# RFBoardLayoutGen0_v03_1routing.net
KiCad netlist of a schematic drawn in EAGLE
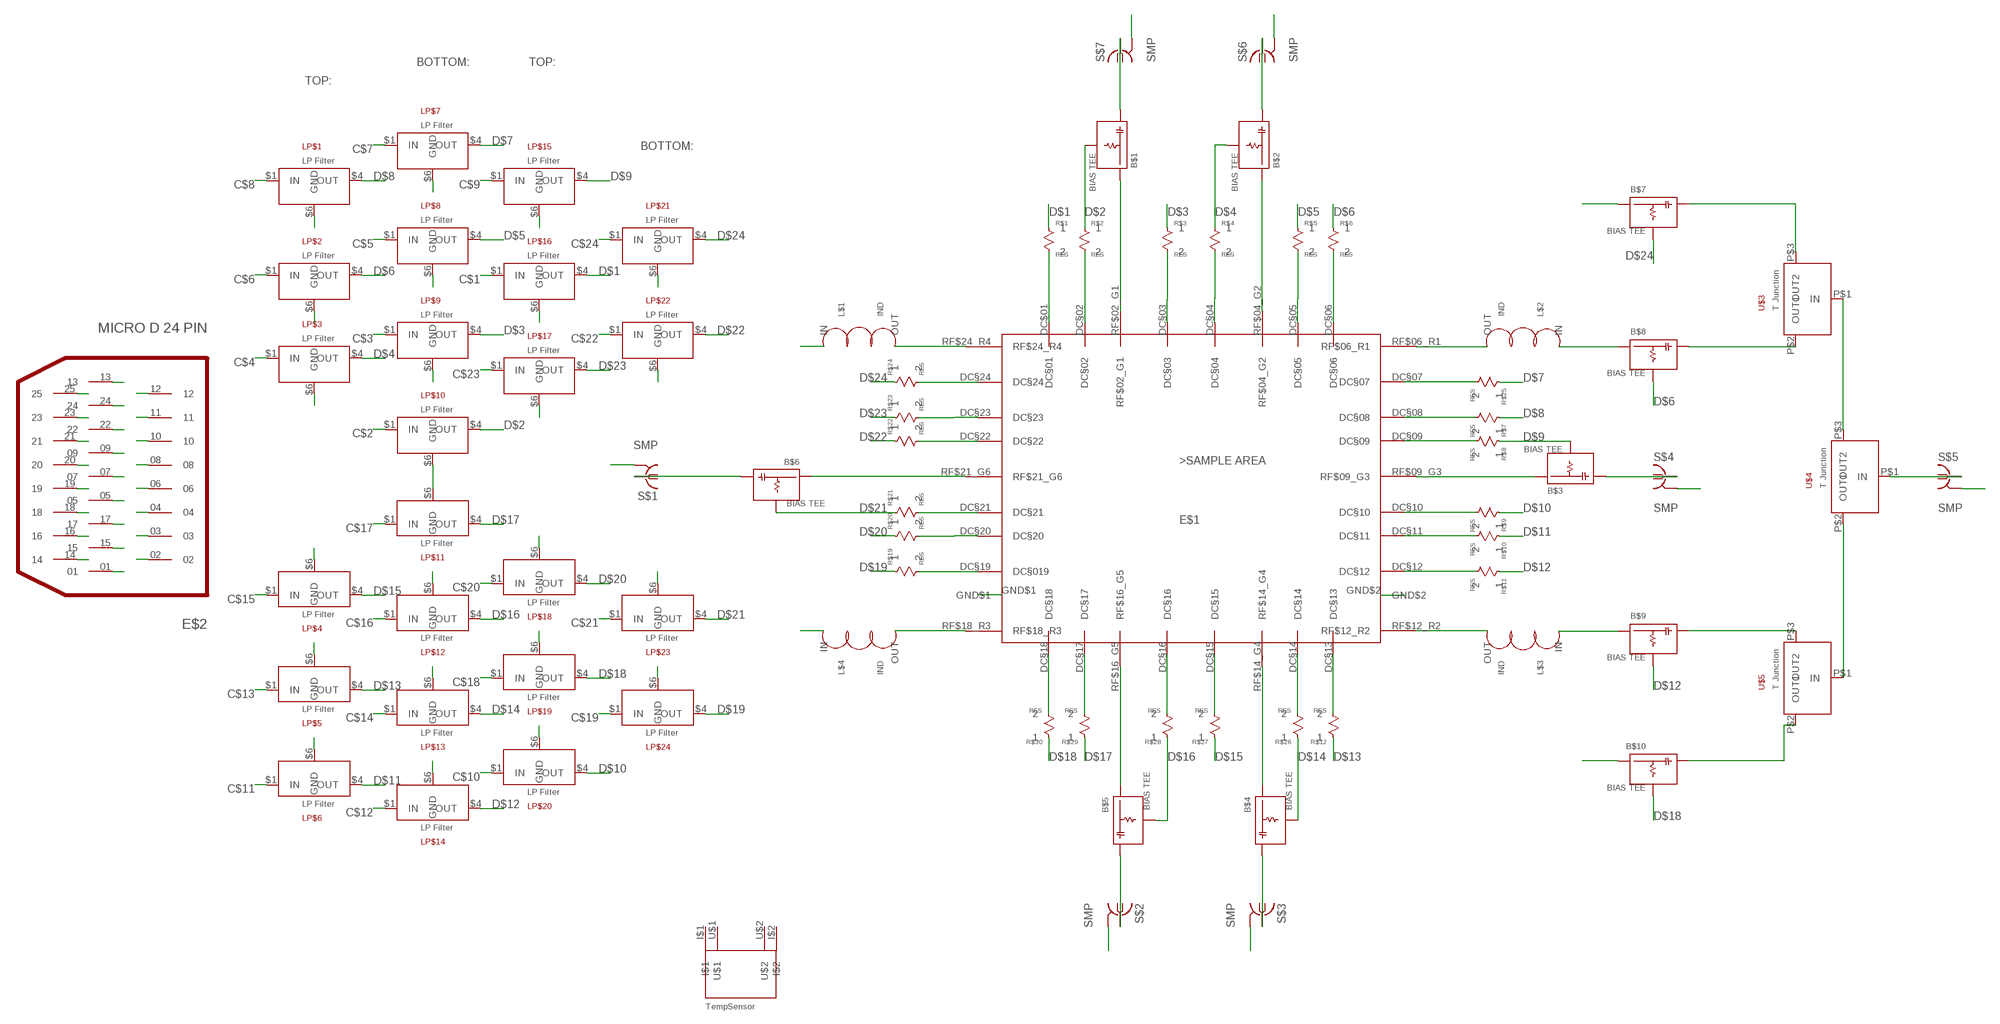
[diagram p0: schematic, sheet 1, part 1 of 2]
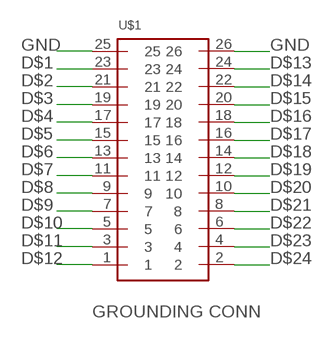
[diagram p1: schematic, sheet 1, part 2 of 2]

(export (version "E")
  (design (tool "Eeschema 10.0.6"))
  (components
    (comp (ref "B$1")
      (value "BIASTEEDOWN")
      (footprint "eagle-import:BIAS_TEE_DOWN_0603")
      (libsource (lib "eagle-import") (part "BIASTEEDOWN"))
    )
    (comp (ref "B$2")
      (value "BIASTEEUP")
      (footprint "eagle-import:BIAS_TEE_UP_0603")
      (libsource (lib "eagle-import") (part "BIASTEEUP"))
    )
    (comp (ref "B$3")
      (value "BIASTEEDOWN")
      (footprint "eagle-import:BIAS_TEE_DOWN_0603")
      (libsource (lib "eagle-import") (part "BIASTEEDOWN"))
    )
    (comp (ref "B$4")
      (value "BIASTEEDOWN")
      (footprint "eagle-import:BIAS_TEE_DOWN_0603")
      (libsource (lib "eagle-import") (part "BIASTEEDOWN"))
    )
    (comp (ref "B$5")
      (value "BIASTEEUP")
      (footprint "eagle-import:BIAS_TEE_UP_0603")
      (libsource (lib "eagle-import") (part "BIASTEEUP"))
    )
    (comp (ref "B$6")
      (value "BIASTEEDOWN")
      (footprint "eagle-import:BIAS_TEE_DOWN_0603")
      (libsource (lib "eagle-import") (part "BIASTEEDOWN"))
    )
    (comp (ref "B$7")
      (value "BIASTEEUP")
      (footprint "eagle-import:BIAS_TEE_UP_0603")
      (libsource (lib "eagle-import") (part "BIASTEEUP"))
    )
    (comp (ref "B$8")
      (value "BIASTEEDOWN")
      (footprint "eagle-import:BIAS_TEE_DOWN_0603")
      (libsource (lib "eagle-import") (part "BIASTEEDOWN"))
    )
    (comp (ref "B$9")
      (value "BIASTEEUP")
      (footprint "eagle-import:BIAS_TEE_UP_0603")
      (libsource (lib "eagle-import") (part "BIASTEEUP"))
    )
    (comp (ref "B$10")
      (value "BIASTEEDOWN")
      (footprint "eagle-import:BIAS_TEE_DOWN_0603")
      (libsource (lib "eagle-import") (part "BIASTEEDOWN"))
    )
    (comp (ref "E$1")
      (value "24DC+10RF")
      (footprint "eagle-import:24DC+10RF_400MU-PADS_0.7X0.7_V1.0")
      (libsource (lib "eagle-import") (part "24DC+10RF"))
    )
    (comp (ref "E$2")
      (value "25_SOCKET_M83513(13-DPINOUT2")
      (footprint "eagle-import:25_SOCKET_M83513_13-D_V2")
      (libsource (lib "eagle-import") (part "25_SOCKET_M83513(13-DPINOUT2"))
    )
    (comp (ref "L$1")
      (value "L_MATCH")
      (footprint "eagle-import:L_MATCH")
      (libsource (lib "eagle-import") (part "L_MATCH"))
    )
    (comp (ref "L$2")
      (value "L_MATCH")
      (footprint "eagle-import:L_MATCH")
      (libsource (lib "eagle-import") (part "L_MATCH"))
    )
    (comp (ref "L$3")
      (value "L_MATCH")
      (footprint "eagle-import:L_MATCH")
      (libsource (lib "eagle-import") (part "L_MATCH"))
    )
    (comp (ref "L$4")
      (value "L_MATCH")
      (footprint "eagle-import:L_MATCH")
      (libsource (lib "eagle-import") (part "L_MATCH"))
    )
    (comp (ref "LP$1")
      (value "LP-FILTER/1-STAGETOP")
      (footprint "eagle-import:LP-FILTER_1_STAGE_OS_0603_TOP")
      (libsource (lib "eagle-import") (part "LP-FILTER/1-STAGETOP"))
    )
    (comp (ref "LP$2")
      (value "LP-FILTER/1-STAGETOP")
      (footprint "eagle-import:LP-FILTER_1_STAGE_OS_0603_TOP")
      (libsource (lib "eagle-import") (part "LP-FILTER/1-STAGETOP"))
    )
    (comp (ref "LP$3")
      (value "LP-FILTER/1-STAGETOP")
      (footprint "eagle-import:LP-FILTER_1_STAGE_OS_0603_TOP")
      (libsource (lib "eagle-import") (part "LP-FILTER/1-STAGETOP"))
    )
    (comp (ref "LP$4")
      (value "LP-FILTER/1-STAGETOP")
      (footprint "eagle-import:LP-FILTER_1_STAGE_OS_0603_TOP")
      (libsource (lib "eagle-import") (part "LP-FILTER/1-STAGETOP"))
    )
    (comp (ref "LP$5")
      (value "LP-FILTER/1-STAGETOP")
      (footprint "eagle-import:LP-FILTER_1_STAGE_OS_0603_TOP")
      (libsource (lib "eagle-import") (part "LP-FILTER/1-STAGETOP"))
    )
    (comp (ref "LP$6")
      (value "LP-FILTER/1-STAGETOP")
      (footprint "eagle-import:LP-FILTER_1_STAGE_OS_0603_TOP")
      (libsource (lib "eagle-import") (part "LP-FILTER/1-STAGETOP"))
    )
    (comp (ref "LP$7")
      (value "LP-FILTER/1-STAGEBOT")
      (footprint "eagle-import:LP-FILTER_1_STAGE_OS_0603_BOTTOM")
      (libsource (lib "eagle-import") (part "LP-FILTER/1-STAGEBOT"))
    )
    (comp (ref "LP$8")
      (value "LP-FILTER/1-STAGEBOT")
      (footprint "eagle-import:LP-FILTER_1_STAGE_OS_0603_BOTTOM")
      (libsource (lib "eagle-import") (part "LP-FILTER/1-STAGEBOT"))
    )
    (comp (ref "LP$9")
      (value "LP-FILTER/1-STAGEBOT")
      (footprint "eagle-import:LP-FILTER_1_STAGE_OS_0603_BOTTOM")
      (libsource (lib "eagle-import") (part "LP-FILTER/1-STAGEBOT"))
    )
    (comp (ref "LP$10")
      (value "LP-FILTER/1-STAGEBOT")
      (footprint "eagle-import:LP-FILTER_1_STAGE_OS_0603_BOTTOM")
      (libsource (lib "eagle-import") (part "LP-FILTER/1-STAGEBOT"))
    )
    (comp (ref "LP$11")
      (value "LP-FILTER/1-STAGEBOT")
      (footprint "eagle-import:LP-FILTER_1_STAGE_OS_0603_BOTTOM")
      (libsource (lib "eagle-import") (part "LP-FILTER/1-STAGEBOT"))
    )
    (comp (ref "LP$12")
      (value "LP-FILTER/1-STAGEBOT")
      (footprint "eagle-import:LP-FILTER_1_STAGE_OS_0603_BOTTOM")
      (libsource (lib "eagle-import") (part "LP-FILTER/1-STAGEBOT"))
    )
    (comp (ref "LP$13")
      (value "LP-FILTER/1-STAGEBOT")
      (footprint "eagle-import:LP-FILTER_1_STAGE_OS_0603_BOTTOM")
      (libsource (lib "eagle-import") (part "LP-FILTER/1-STAGEBOT"))
    )
    (comp (ref "LP$14")
      (value "LP-FILTER/1-STAGEBOT")
      (footprint "eagle-import:LP-FILTER_1_STAGE_OS_0603_BOTTOM")
      (libsource (lib "eagle-import") (part "LP-FILTER/1-STAGEBOT"))
    )
    (comp (ref "LP$15")
      (value "LP-FILTER/1-STAGETOP")
      (footprint "eagle-import:LP-FILTER_1_STAGE_OS_0603_TOP")
      (libsource (lib "eagle-import") (part "LP-FILTER/1-STAGETOP"))
    )
    (comp (ref "LP$16")
      (value "LP-FILTER/1-STAGETOP")
      (footprint "eagle-import:LP-FILTER_1_STAGE_OS_0603_TOP")
      (libsource (lib "eagle-import") (part "LP-FILTER/1-STAGETOP"))
    )
    (comp (ref "LP$17")
      (value "LP-FILTER/1-STAGETOP")
      (footprint "eagle-import:LP-FILTER_1_STAGE_OS_0603_TOP")
      (libsource (lib "eagle-import") (part "LP-FILTER/1-STAGETOP"))
    )
    (comp (ref "LP$18")
      (value "LP-FILTER/1-STAGETOP")
      (footprint "eagle-import:LP-FILTER_1_STAGE_OS_0603_TOP")
      (libsource (lib "eagle-import") (part "LP-FILTER/1-STAGETOP"))
    )
    (comp (ref "LP$19")
      (value "LP-FILTER/1-STAGETOP")
      (footprint "eagle-import:LP-FILTER_1_STAGE_OS_0603_TOP")
      (libsource (lib "eagle-import") (part "LP-FILTER/1-STAGETOP"))
    )
    (comp (ref "LP$20")
      (value "LP-FILTER/1-STAGETOP")
      (footprint "eagle-import:LP-FILTER_1_STAGE_OS_0603_TOP")
      (libsource (lib "eagle-import") (part "LP-FILTER/1-STAGETOP"))
    )
    (comp (ref "LP$21")
      (value "LP-FILTER/1-STAGEBOT")
      (footprint "eagle-import:LP-FILTER_1_STAGE_OS_0603_BOTTOM")
      (libsource (lib "eagle-import") (part "LP-FILTER/1-STAGEBOT"))
    )
    (comp (ref "LP$22")
      (value "LP-FILTER/1-STAGEBOT")
      (footprint "eagle-import:LP-FILTER_1_STAGE_OS_0603_BOTTOM")
      (libsource (lib "eagle-import") (part "LP-FILTER/1-STAGEBOT"))
    )
    (comp (ref "LP$23")
      (value "LP-FILTER/1-STAGEBOT")
      (footprint "eagle-import:LP-FILTER_1_STAGE_OS_0603_BOTTOM")
      (libsource (lib "eagle-import") (part "LP-FILTER/1-STAGEBOT"))
    )
    (comp (ref "LP$24")
      (value "LP-FILTER/1-STAGEBOT")
      (footprint "eagle-import:LP-FILTER_1_STAGE_OS_0603_BOTTOM")
      (libsource (lib "eagle-import") (part "LP-FILTER/1-STAGEBOT"))
    )
    (comp (ref "R$1")
      (value "10K")
      (footprint "eagle-import:LP-FILTER_RESISTOR_0603_BOTTOM")
      (libsource (lib "eagle-import") (part "LP-FILTER/RESISTOR/0603"))
    )
    (comp (ref "R$2")
      (value "10K")
      (footprint "eagle-import:LP-FILTER_RESISTOR_0603_BOTTOM")
      (libsource (lib "eagle-import") (part "LP-FILTER/RESISTOR/0603"))
    )
    (comp (ref "R$3")
      (value "10K")
      (footprint "eagle-import:LP-FILTER_RESISTOR_0603_BOTTOM")
      (libsource (lib "eagle-import") (part "LP-FILTER/RESISTOR/0603"))
    )
    (comp (ref "R$4")
      (value "10K")
      (footprint "eagle-import:LP-FILTER_RESISTOR_0603_BOTTOM")
      (libsource (lib "eagle-import") (part "LP-FILTER/RESISTOR/0603"))
    )
    (comp (ref "R$5")
      (value "10K")
      (footprint "eagle-import:LP-FILTER_RESISTOR_0603_BOTTOM")
      (libsource (lib "eagle-import") (part "LP-FILTER/RESISTOR/0603"))
    )
    (comp (ref "R$6")
      (value "10K")
      (footprint "eagle-import:LP-FILTER_RESISTOR_0603_BOTTOM")
      (libsource (lib "eagle-import") (part "LP-FILTER/RESISTOR/0603"))
    )
    (comp (ref "R$7")
      (value "10K")
      (footprint "eagle-import:LP-FILTER_RESISTOR_0603_BOTTOM")
      (libsource (lib "eagle-import") (part "LP-FILTER/RESISTOR/0603"))
    )
    (comp (ref "R$8")
      (value "10K")
      (footprint "eagle-import:LP-FILTER_RESISTOR_0603_BOTTOM")
      (libsource (lib "eagle-import") (part "LP-FILTER/RESISTOR/0603"))
    )
    (comp (ref "R$9")
      (value "10K")
      (footprint "eagle-import:LP-FILTER_RESISTOR_0603_BOTTOM")
      (libsource (lib "eagle-import") (part "LP-FILTER/RESISTOR/0603"))
    )
    (comp (ref "R$10")
      (value "10K")
      (footprint "eagle-import:LP-FILTER_RESISTOR_0603_BOTTOM")
      (libsource (lib "eagle-import") (part "LP-FILTER/RESISTOR/0603"))
    )
    (comp (ref "R$11")
      (value "10K")
      (footprint "eagle-import:LP-FILTER_RESISTOR_0603_BOTTOM")
      (libsource (lib "eagle-import") (part "LP-FILTER/RESISTOR/0603"))
    )
    (comp (ref "R$12")
      (value "10K")
      (footprint "eagle-import:LP-FILTER_RESISTOR_0603_BOTTOM")
      (libsource (lib "eagle-import") (part "LP-FILTER/RESISTOR/0603"))
    )
    (comp (ref "R$19")
      (value "10K")
      (footprint "eagle-import:LP-FILTER_RESISTOR_0603_BOTTOM")
      (libsource (lib "eagle-import") (part "LP-FILTER/RESISTOR/0603"))
    )
    (comp (ref "R$20")
      (value "10K")
      (footprint "eagle-import:LP-FILTER_RESISTOR_0603_BOTTOM")
      (libsource (lib "eagle-import") (part "LP-FILTER/RESISTOR/0603"))
    )
    (comp (ref "R$21")
      (value "10K")
      (footprint "eagle-import:LP-FILTER_RESISTOR_0603_BOTTOM")
      (libsource (lib "eagle-import") (part "LP-FILTER/RESISTOR/0603"))
    )
    (comp (ref "R$22")
      (value "10K")
      (footprint "eagle-import:LP-FILTER_RESISTOR_0603_BOTTOM")
      (libsource (lib "eagle-import") (part "LP-FILTER/RESISTOR/0603"))
    )
    (comp (ref "R$23")
      (value "10K")
      (footprint "eagle-import:LP-FILTER_RESISTOR_0603_BOTTOM")
      (libsource (lib "eagle-import") (part "LP-FILTER/RESISTOR/0603"))
    )
    (comp (ref "R$24")
      (value "10K")
      (footprint "eagle-import:LP-FILTER_RESISTOR_0603_BOTTOM")
      (libsource (lib "eagle-import") (part "LP-FILTER/RESISTOR/0603"))
    )
    (comp (ref "R$25")
      (value "10K")
      (footprint "eagle-import:LP-FILTER_RESISTOR_0603_BOTTOM")
      (libsource (lib "eagle-import") (part "LP-FILTER/RESISTOR/0603"))
    )
    (comp (ref "R$26")
      (value "10K")
      (footprint "eagle-import:LP-FILTER_RESISTOR_0603_BOTTOM")
      (libsource (lib "eagle-import") (part "LP-FILTER/RESISTOR/0603"))
    )
    (comp (ref "R$27")
      (value "10K")
      (footprint "eagle-import:LP-FILTER_RESISTOR_0603_BOTTOM")
      (libsource (lib "eagle-import") (part "LP-FILTER/RESISTOR/0603"))
    )
    (comp (ref "R$28")
      (value "10K")
      (footprint "eagle-import:LP-FILTER_RESISTOR_0603_BOTTOM")
      (libsource (lib "eagle-import") (part "LP-FILTER/RESISTOR/0603"))
    )
    (comp (ref "R$29")
      (value "10K")
      (footprint "eagle-import:LP-FILTER_RESISTOR_0603_BOTTOM")
      (libsource (lib "eagle-import") (part "LP-FILTER/RESISTOR/0603"))
    )
    (comp (ref "R$30")
      (value "10K")
      (footprint "eagle-import:LP-FILTER_RESISTOR_0603_BOTTOM")
      (libsource (lib "eagle-import") (part "LP-FILTER/RESISTOR/0603"))
    )
    (comp (ref "S$1")
      (value "MC-921")
      (footprint "eagle-import:SMP_STRAIGHT_MINI")
      (libsource (lib "eagle-import") (part "MC-921"))
    )
    (comp (ref "S$2")
      (value "MC-921")
      (footprint "eagle-import:SMP_STRAIGHT_MINI")
      (libsource (lib "eagle-import") (part "MC-921"))
    )
    (comp (ref "S$3")
      (value "MC-921")
      (footprint "eagle-import:SMP_STRAIGHT_MINI")
      (libsource (lib "eagle-import") (part "MC-921"))
    )
    (comp (ref "S$4")
      (value "MC-921")
      (footprint "eagle-import:SMP_STRAIGHT_MINI")
      (libsource (lib "eagle-import") (part "MC-921"))
    )
    (comp (ref "S$5")
      (value "MC-921")
      (footprint "eagle-import:SMP_STRAIGHT_MINI")
      (libsource (lib "eagle-import") (part "MC-921"))
    )
    (comp (ref "S$6")
      (value "MC-921")
      (footprint "eagle-import:SMP_STRAIGHT_MINI")
      (libsource (lib "eagle-import") (part "MC-921"))
    )
    (comp (ref "S$7")
      (value "MC-921")
      (footprint "eagle-import:SMP_STRAIGHT_MINI")
      (libsource (lib "eagle-import") (part "MC-921"))
    )
    (comp (ref "U$1")
      (value "MEC8-113-02-L-D-RA1MBRD")
      (footprint "eagle-import:MEC8-113-02-L-D-RA1")
      (libsource (lib "eagle-import") (part "MEC8-113-02-L-D-RA1MBRD"))
    )
    (comp (ref "U$2")
      (value "TEMPSENS")
      (footprint "eagle-import:RX-BR_V1")
      (libsource (lib "eagle-import") (part "TEMPSENS"))
    )
    (comp (ref "U$3")
      (value "TJUNCTION")
      (footprint "eagle-import:T_JUNCTION_0.3MM")
      (libsource (lib "eagle-import") (part "TJUNCTION"))
    )
    (comp (ref "U$4")
      (value "TJUNCTION")
      (footprint "eagle-import:T_JUNCTION_0.3MM")
      (libsource (lib "eagle-import") (part "TJUNCTION"))
    )
    (comp (ref "U$5")
      (value "TJUNCTION")
      (footprint "eagle-import:T_JUNCTION_0.3MM")
      (libsource (lib "eagle-import") (part "TJUNCTION"))
    )
  )
  (nets
    (net (code "1") (name "/C$1") (class "Default")
      (node (ref "E$2") (pin "01") (pinfunction "01_01") (pintype "bidirectional"))
      (node (ref "LP$16") (pin "$1") (pinfunction "IN_$1") (pintype "bidirectional"))
    )
    (net (code "2") (name "/C$2") (class "Default")
      (node (ref "E$2") (pin "02") (pinfunction "02_02") (pintype "bidirectional"))
      (node (ref "LP$10") (pin "$1") (pinfunction "IN_$1") (pintype "bidirectional"))
    )
    (net (code "3") (name "/C$3") (class "Default")
      (node (ref "E$2") (pin "03") (pinfunction "03_03") (pintype "bidirectional"))
      (node (ref "LP$9") (pin "$1") (pinfunction "IN_$1") (pintype "bidirectional"))
    )
    (net (code "4") (name "/C$4") (class "Default")
      (node (ref "E$2") (pin "04") (pinfunction "04_04") (pintype "bidirectional"))
      (node (ref "LP$3") (pin "$1") (pinfunction "IN_$1") (pintype "bidirectional"))
    )
    (net (code "5") (name "/C$5") (class "Default")
      (node (ref "E$2") (pin "05") (pinfunction "05_05") (pintype "bidirectional"))
      (node (ref "LP$8") (pin "$1") (pinfunction "IN_$1") (pintype "bidirectional"))
    )
    (net (code "6") (name "/C$6") (class "Default")
      (node (ref "E$2") (pin "06") (pinfunction "06_06") (pintype "bidirectional"))
      (node (ref "LP$2") (pin "$1") (pinfunction "IN_$1") (pintype "bidirectional"))
    )
    (net (code "7") (name "/C$7") (class "Default")
      (node (ref "E$2") (pin "07") (pinfunction "07_07") (pintype "bidirectional"))
      (node (ref "LP$7") (pin "$1") (pinfunction "IN_$1") (pintype "bidirectional"))
    )
    (net (code "8") (name "/C$8") (class "Default")
      (node (ref "E$2") (pin "08") (pinfunction "08_08") (pintype "bidirectional"))
      (node (ref "LP$1") (pin "$1") (pinfunction "IN_$1") (pintype "bidirectional"))
    )
    (net (code "9") (name "/C$9") (class "Default")
      (node (ref "E$2") (pin "09") (pinfunction "09_09") (pintype "bidirectional"))
      (node (ref "LP$15") (pin "$1") (pinfunction "IN_$1") (pintype "bidirectional"))
    )
    (net (code "10") (name "/C$10") (class "Default")
      (node (ref "E$2") (pin "10") (pinfunction "10_10") (pintype "bidirectional"))
      (node (ref "LP$20") (pin "$1") (pinfunction "IN_$1") (pintype "bidirectional"))
    )
    (net (code "11") (name "/C$11") (class "Default")
      (node (ref "E$2") (pin "11") (pinfunction "11_11") (pintype "bidirectional"))
      (node (ref "LP$6") (pin "$1") (pinfunction "IN_$1") (pintype "bidirectional"))
    )
    (net (code "12") (name "/C$12") (class "Default")
      (node (ref "E$2") (pin "12") (pinfunction "12_12") (pintype "bidirectional"))
      (node (ref "LP$14") (pin "$1") (pinfunction "IN_$1") (pintype "bidirectional"))
    )
    (net (code "13") (name "/C$13") (class "Default")
      (node (ref "E$2") (pin "13") (pinfunction "13_13") (pintype "bidirectional"))
      (node (ref "LP$5") (pin "$1") (pinfunction "IN_$1") (pintype "bidirectional"))
    )
    (net (code "14") (name "/C$14") (class "Default")
      (node (ref "E$2") (pin "14") (pinfunction "14_14") (pintype "bidirectional"))
      (node (ref "LP$13") (pin "$1") (pinfunction "IN_$1") (pintype "bidirectional"))
    )
    (net (code "15") (name "/C$15") (class "Default")
      (node (ref "E$2") (pin "15") (pinfunction "15_15") (pintype "bidirectional"))
      (node (ref "LP$4") (pin "$1") (pinfunction "IN_$1") (pintype "bidirectional"))
    )
    (net (code "16") (name "/C$16") (class "Default")
      (node (ref "E$2") (pin "16") (pinfunction "16_16") (pintype "bidirectional"))
      (node (ref "LP$12") (pin "$1") (pinfunction "IN_$1") (pintype "bidirectional"))
    )
    (net (code "17") (name "/C$17") (class "Default")
      (node (ref "E$2") (pin "17") (pinfunction "17_17") (pintype "bidirectional"))
      (node (ref "LP$11") (pin "$1") (pinfunction "IN_$1") (pintype "bidirectional"))
    )
    (net (code "18") (name "/C$18") (class "Default")
      (node (ref "E$2") (pin "18") (pinfunction "18_18") (pintype "bidirectional"))
      (node (ref "LP$19") (pin "$1") (pinfunction "IN_$1") (pintype "bidirectional"))
    )
    (net (code "19") (name "/C$19") (class "Default")
      (node (ref "E$2") (pin "19") (pinfunction "19_19") (pintype "bidirectional"))
      (node (ref "LP$24") (pin "$1") (pinfunction "IN_$1") (pintype "bidirectional"))
    )
    (net (code "20") (name "/C$20") (class "Default")
      (node (ref "E$2") (pin "20") (pinfunction "20_20") (pintype "bidirectional"))
      (node (ref "LP$18") (pin "$1") (pinfunction "IN_$1") (pintype "bidirectional"))
    )
    (net (code "21") (name "/C$21") (class "Default")
      (node (ref "E$2") (pin "21") (pinfunction "21_21") (pintype "bidirectional"))
      (node (ref "LP$23") (pin "$1") (pinfunction "IN_$1") (pintype "bidirectional"))
    )
    (net (code "22") (name "/C$22") (class "Default")
      (node (ref "E$2") (pin "22") (pinfunction "22_22") (pintype "bidirectional"))
      (node (ref "LP$22") (pin "$1") (pinfunction "IN_$1") (pintype "bidirectional"))
    )
    (net (code "23") (name "/C$23") (class "Default")
      (node (ref "E$2") (pin "23") (pinfunction "23_23") (pintype "bidirectional"))
      (node (ref "LP$17") (pin "$1") (pinfunction "IN_$1") (pintype "bidirectional"))
    )
    (net (code "24") (name "/C$24") (class "Default")
      (node (ref "E$2") (pin "24") (pinfunction "24_24") (pintype "bidirectional"))
      (node (ref "LP$21") (pin "$1") (pinfunction "IN_$1") (pintype "bidirectional"))
    )
    (net (code "25") (name "/D$1") (class "Default")
      (node (ref "LP$16") (pin "$4") (pinfunction "OUT_$4") (pintype "bidirectional"))
      (node (ref "R$1") (pin "IN") (pinfunction "1_IN") (pintype "passive"))
      (node (ref "U$1") (pin "23") (pinfunction "23_23") (pintype "bidirectional"))
    )
    (net (code "26") (name "/D$2") (class "Default")
      (node (ref "B$1") (pin "LF") (pinfunction "LF_LF") (pintype "bidirectional"))
      (node (ref "LP$10") (pin "$4") (pinfunction "OUT_$4") (pintype "bidirectional"))
      (node (ref "R$2") (pin "IN") (pinfunction "1_IN") (pintype "passive"))
      (node (ref "U$1") (pin "21") (pinfunction "21_21") (pintype "bidirectional"))
    )
    (net (code "27") (name "/D$3") (class "Default")
      (node (ref "LP$9") (pin "$4") (pinfunction "OUT_$4") (pintype "bidirectional"))
      (node (ref "R$3") (pin "IN") (pinfunction "1_IN") (pintype "passive"))
      (node (ref "U$1") (pin "19") (pinfunction "19_19") (pintype "bidirectional"))
    )
    (net (code "28") (name "/D$4") (class "Default")
      (node (ref "B$2") (pin "LF") (pinfunction "LF_LF") (pintype "bidirectional"))
      (node (ref "LP$3") (pin "$4") (pinfunction "OUT_$4") (pintype "bidirectional"))
      (node (ref "R$4") (pin "IN") (pinfunction "1_IN") (pintype "passive"))
      (node (ref "U$1") (pin "17") (pinfunction "17_17") (pintype "bidirectional"))
    )
    (net (code "29") (name "/D$5") (class "Default")
      (node (ref "LP$8") (pin "$4") (pinfunction "OUT_$4") (pintype "bidirectional"))
      (node (ref "R$5") (pin "IN") (pinfunction "1_IN") (pintype "passive"))
      (node (ref "U$1") (pin "15") (pinfunction "15_15") (pintype "bidirectional"))
    )
    (net (code "30") (name "/D$6") (class "Default")
      (node (ref "B$8") (pin "LF") (pinfunction "LF_LF") (pintype "bidirectional"))
      (node (ref "LP$2") (pin "$4") (pinfunction "OUT_$4") (pintype "bidirectional"))
      (node (ref "R$6") (pin "IN") (pinfunction "1_IN") (pintype "passive"))
      (node (ref "U$1") (pin "13") (pinfunction "13_13") (pintype "bidirectional"))
    )
    (net (code "31") (name "/D$7") (class "Default")
      (node (ref "LP$7") (pin "$4") (pinfunction "OUT_$4") (pintype "bidirectional"))
      (node (ref "R$25") (pin "IN") (pinfunction "1_IN") (pintype "passive"))
      (node (ref "U$1") (pin "11") (pinfunction "11_11") (pintype "bidirectional"))
    )
    (net (code "32") (name "/D$8") (class "Default")
      (node (ref "LP$1") (pin "$4") (pinfunction "OUT_$4") (pintype "bidirectional"))
      (node (ref "R$7") (pin "IN") (pinfunction "1_IN") (pintype "passive"))
      (node (ref "U$1") (pin "9") (pinfunction "9_9") (pintype "bidirectional"))
    )
    (net (code "33") (name "/D$9") (class "Default")
      (node (ref "B$3") (pin "LF") (pinfunction "LF_LF") (pintype "bidirectional"))
      (node (ref "LP$15") (pin "$4") (pinfunction "OUT_$4") (pintype "bidirectional"))
      (node (ref "R$8") (pin "IN") (pinfunction "1_IN") (pintype "passive"))
      (node (ref "U$1") (pin "7") (pinfunction "7_7") (pintype "bidirectional"))
    )
    (net (code "34") (name "/D$10") (class "Default")
      (node (ref "LP$20") (pin "$4") (pinfunction "OUT_$4") (pintype "bidirectional"))
      (node (ref "R$9") (pin "IN") (pinfunction "1_IN") (pintype "passive"))
      (node (ref "U$1") (pin "5") (pinfunction "5_5") (pintype "bidirectional"))
    )
    (net (code "35") (name "/D$11") (class "Default")
      (node (ref "LP$6") (pin "$4") (pinfunction "OUT_$4") (pintype "bidirectional"))
      (node (ref "R$10") (pin "IN") (pinfunction "1_IN") (pintype "passive"))
      (node (ref "U$1") (pin "3") (pinfunction "3_3") (pintype "bidirectional"))
    )
    (net (code "36") (name "/D$12") (class "Default")
      (node (ref "B$9") (pin "LF") (pinfunction "LF_LF") (pintype "bidirectional"))
      (node (ref "LP$14") (pin "$4") (pinfunction "OUT_$4") (pintype "bidirectional"))
      (node (ref "R$11") (pin "IN") (pinfunction "1_IN") (pintype "passive"))
      (node (ref "U$1") (pin "1") (pinfunction "1_1") (pintype "bidirectional"))
    )
    (net (code "37") (name "/D$13") (class "Default")
      (node (ref "LP$5") (pin "$4") (pinfunction "OUT_$4") (pintype "bidirectional"))
      (node (ref "R$12") (pin "IN") (pinfunction "1_IN") (pintype "passive"))
      (node (ref "U$1") (pin "24") (pinfunction "24_24") (pintype "bidirectional"))
    )
    (net (code "38") (name "/D$14") (class "Default")
      (node (ref "B$4") (pin "LF") (pinfunction "LF_LF") (pintype "bidirectional"))
      (node (ref "LP$13") (pin "$4") (pinfunction "OUT_$4") (pintype "bidirectional"))
      (node (ref "R$26") (pin "IN") (pinfunction "1_IN") (pintype "passive"))
      (node (ref "U$1") (pin "22") (pinfunction "22_22") (pintype "bidirectional"))
    )
    (net (code "39") (name "/D$15") (class "Default")
      (node (ref "LP$4") (pin "$4") (pinfunction "OUT_$4") (pintype "bidirectional"))
      (node (ref "R$27") (pin "IN") (pinfunction "1_IN") (pintype "passive"))
      (node (ref "U$1") (pin "20") (pinfunction "20_20") (pintype "bidirectional"))
    )
    (net (code "40") (name "/D$16") (class "Default")
      (node (ref "B$5") (pin "LF") (pinfunction "LF_LF") (pintype "bidirectional"))
      (node (ref "LP$12") (pin "$4") (pinfunction "OUT_$4") (pintype "bidirectional"))
      (node (ref "R$28") (pin "IN") (pinfunction "1_IN") (pintype "passive"))
      (node (ref "U$1") (pin "18") (pinfunction "18_18") (pintype "bidirectional"))
    )
    (net (code "41") (name "/D$17") (class "Default")
      (node (ref "LP$11") (pin "$4") (pinfunction "OUT_$4") (pintype "bidirectional"))
      (node (ref "R$29") (pin "IN") (pinfunction "1_IN") (pintype "passive"))
      (node (ref "U$1") (pin "16") (pinfunction "16_16") (pintype "bidirectional"))
    )
    (net (code "42") (name "/D$18") (class "Default")
      (node (ref "B$10") (pin "LF") (pinfunction "LF_LF") (pintype "bidirectional"))
      (node (ref "LP$19") (pin "$4") (pinfunction "OUT_$4") (pintype "bidirectional"))
      (node (ref "R$30") (pin "IN") (pinfunction "1_IN") (pintype "passive"))
      (node (ref "U$1") (pin "14") (pinfunction "14_14") (pintype "bidirectional"))
    )
    (net (code "43") (name "/D$19") (class "Default")
      (node (ref "LP$24") (pin "$4") (pinfunction "OUT_$4") (pintype "bidirectional"))
      (node (ref "R$19") (pin "IN") (pinfunction "1_IN") (pintype "passive"))
      (node (ref "U$1") (pin "12") (pinfunction "12_12") (pintype "bidirectional"))
    )
    (net (code "44") (name "/D$20") (class "Default")
      (node (ref "LP$18") (pin "$4") (pinfunction "OUT_$4") (pintype "bidirectional"))
      (node (ref "R$20") (pin "IN") (pinfunction "1_IN") (pintype "passive"))
      (node (ref "U$1") (pin "10") (pinfunction "10_10") (pintype "bidirectional"))
    )
    (net (code "45") (name "/D$21") (class "Default")
      (node (ref "B$6") (pin "LF") (pinfunction "LF_LF") (pintype "bidirectional"))
      (node (ref "LP$23") (pin "$4") (pinfunction "OUT_$4") (pintype "bidirectional"))
      (node (ref "R$21") (pin "IN") (pinfunction "1_IN") (pintype "passive"))
      (node (ref "U$1") (pin "8") (pinfunction "8_8") (pintype "bidirectional"))
    )
    (net (code "46") (name "/D$22") (class "Default")
      (node (ref "LP$22") (pin "$4") (pinfunction "OUT_$4") (pintype "bidirectional"))
      (node (ref "R$22") (pin "IN") (pinfunction "1_IN") (pintype "passive"))
      (node (ref "U$1") (pin "6") (pinfunction "6_6") (pintype "bidirectional"))
    )
    (net (code "47") (name "/D$23") (class "Default")
      (node (ref "LP$17") (pin "$4") (pinfunction "OUT_$4") (pintype "bidirectional"))
      (node (ref "R$23") (pin "IN") (pinfunction "1_IN") (pintype "passive"))
      (node (ref "U$1") (pin "4") (pinfunction "4_4") (pintype "bidirectional"))
    )
    (net (code "48") (name "/D$24") (class "Default")
      (node (ref "B$7") (pin "LF") (pinfunction "LF_LF") (pintype "bidirectional"))
      (node (ref "LP$21") (pin "$4") (pinfunction "OUT_$4") (pintype "bidirectional"))
      (node (ref "R$24") (pin "IN") (pinfunction "1_IN") (pintype "passive"))
      (node (ref "U$1") (pin "2") (pinfunction "2_2") (pintype "bidirectional"))
    )
    (net (code "49") (name "/GND") (class "Default")
      (node (ref "E$1") (pin "GND$1") (pinfunction "GND$1_GND$1") (pintype "bidirectional"))
      (node (ref "E$1") (pin "GND$2") (pinfunction "GND$2_GND$2") (pintype "bidirectional"))
      (node (ref "E$2") (pin "25") (pinfunction "25_25") (pintype "bidirectional"))
      (node (ref "LP$1") (pin "$6") (pinfunction "GND_$6") (pintype "bidirectional"))
      (node (ref "LP$10") (pin "$6") (pinfunction "GND_$6") (pintype "bidirectional"))
      (node (ref "LP$11") (pin "$6") (pinfunction "GND_$6") (pintype "bidirectional"))
      (node (ref "LP$12") (pin "$6") (pinfunction "GND_$6") (pintype "bidirectional"))
      (node (ref "LP$13") (pin "$6") (pinfunction "GND_$6") (pintype "bidirectional"))
      (node (ref "LP$14") (pin "$6") (pinfunction "GND_$6") (pintype "bidirectional"))
      (node (ref "LP$15") (pin "$6") (pinfunction "GND_$6") (pintype "bidirectional"))
      (node (ref "LP$16") (pin "$6") (pinfunction "GND_$6") (pintype "bidirectional"))
      (node (ref "LP$17") (pin "$6") (pinfunction "GND_$6") (pintype "bidirectional"))
      (node (ref "LP$18") (pin "$6") (pinfunction "GND_$6") (pintype "bidirectional"))
      (node (ref "LP$19") (pin "$6") (pinfunction "GND_$6") (pintype "bidirectional"))
      (node (ref "LP$2") (pin "$6") (pinfunction "GND_$6") (pintype "bidirectional"))
      (node (ref "LP$20") (pin "$6") (pinfunction "GND_$6") (pintype "bidirectional"))
      (node (ref "LP$21") (pin "$6") (pinfunction "GND_$6") (pintype "bidirectional"))
      (node (ref "LP$22") (pin "$6") (pinfunction "GND_$6") (pintype "bidirectional"))
      (node (ref "LP$23") (pin "$6") (pinfunction "GND_$6") (pintype "bidirectional"))
      (node (ref "LP$24") (pin "$6") (pinfunction "GND_$6") (pintype "bidirectional"))
      (node (ref "LP$3") (pin "$6") (pinfunction "GND_$6") (pintype "bidirectional"))
      (node (ref "LP$4") (pin "$6") (pinfunction "GND_$6") (pintype "bidirectional"))
      (node (ref "LP$5") (pin "$6") (pinfunction "GND_$6") (pintype "bidirectional"))
      (node (ref "LP$6") (pin "$6") (pinfunction "GND_$6") (pintype "bidirectional"))
      (node (ref "LP$7") (pin "$6") (pinfunction "GND_$6") (pintype "bidirectional"))
      (node (ref "LP$8") (pin "$6") (pinfunction "GND_$6") (pintype "bidirectional"))
      (node (ref "LP$9") (pin "$6") (pinfunction "GND_$6") (pintype "bidirectional"))
      (node (ref "S$1") (pin "2@1") (pinfunction "GND_2@1") (pintype "passive"))
      (node (ref "S$1") (pin "2@2") (pinfunction "GND_2@2") (pintype "passive"))
      (node (ref "S$2") (pin "2@1") (pinfunction "GND_2@1") (pintype "passive"))
      (node (ref "S$2") (pin "2@2") (pinfunction "GND_2@2") (pintype "passive"))
      (node (ref "S$3") (pin "2@1") (pinfunction "GND_2@1") (pintype "passive"))
      (node (ref "S$3") (pin "2@2") (pinfunction "GND_2@2") (pintype "passive"))
      (node (ref "S$4") (pin "2@1") (pinfunction "GND_2@1") (pintype "passive"))
      (node (ref "S$4") (pin "2@2") (pinfunction "GND_2@2") (pintype "passive"))
      (node (ref "S$5") (pin "2@1") (pinfunction "GND_2@1") (pintype "passive"))
      (node (ref "S$5") (pin "2@2") (pinfunction "GND_2@2") (pintype "passive"))
      (node (ref "S$6") (pin "2@1") (pinfunction "GND_2@1") (pintype "passive"))
      (node (ref "S$6") (pin "2@2") (pinfunction "GND_2@2") (pintype "passive"))
      (node (ref "S$7") (pin "2@1") (pinfunction "GND_2@1") (pintype "passive"))
      (node (ref "S$7") (pin "2@2") (pinfunction "GND_2@2") (pintype "passive"))
      (node (ref "U$1") (pin "25") (pinfunction "25_25") (pintype "bidirectional"))
      (node (ref "U$1") (pin "26") (pinfunction "26_26") (pintype "bidirectional"))
    )
    (net (code "50") (name "/RF$3") (class "Default")
      (node (ref "B$10") (pin "OUT") (pinfunction "OUT_OUT") (pintype "bidirectional"))
      (node (ref "L$4") (pin "IN") (pinfunction "IN_IN") (pintype "passive"))
    )
    (net (code "51") (name "/RF$4") (class "Default")
      (node (ref "B$7") (pin "OUT") (pinfunction "OUT_OUT") (pintype "bidirectional"))
      (node (ref "L$1") (pin "IN") (pinfunction "IN_IN") (pintype "passive"))
    )
    (net (code "52") (name "Net-(B$1-PadHF)") (class "Default")
      (node (ref "B$1") (pin "HF") (pinfunction "HF_HF") (pintype "bidirectional"))
      (node (ref "S$7") (pin "1") (pinfunction "1_1") (pintype "passive"))
    )
    (net (code "53") (name "Net-(B$1-PadOUT)") (class "Default")
      (node (ref "B$1") (pin "OUT") (pinfunction "OUT_OUT") (pintype "bidirectional"))
      (node (ref "E$1") (pin "RF$02_G1") (pinfunction "RF$02_G1_RF$02_G1") (pintype "bidirectional"))
    )
    (net (code "54") (name "Net-(B$2-PadHF)") (class "Default")
      (node (ref "B$2") (pin "HF") (pinfunction "HF_HF") (pintype "bidirectional"))
      (node (ref "S$6") (pin "1") (pinfunction "1_1") (pintype "passive"))
    )
    (net (code "55") (name "Net-(B$2-PadOUT)") (class "Default")
      (node (ref "B$2") (pin "OUT") (pinfunction "OUT_OUT") (pintype "bidirectional"))
      (node (ref "E$1") (pin "RF$04_G2") (pinfunction "RF$04_G2_RF$04_G2") (pintype "bidirectional"))
    )
    (net (code "56") (name "Net-(B$3-PadHF)") (class "Default")
      (node (ref "B$3") (pin "HF") (pinfunction "HF_HF") (pintype "bidirectional"))
      (node (ref "S$4") (pin "1") (pinfunction "1_1") (pintype "passive"))
    )
    (net (code "57") (name "Net-(B$3-PadOUT)") (class "Default")
      (node (ref "B$3") (pin "OUT") (pinfunction "OUT_OUT") (pintype "bidirectional"))
      (node (ref "E$1") (pin "RF$09_G3") (pinfunction "RF$09_G3_RF$09_G3") (pintype "bidirectional"))
    )
    (net (code "58") (name "Net-(B$4-PadHF)") (class "Default")
      (node (ref "B$4") (pin "HF") (pinfunction "HF_HF") (pintype "bidirectional"))
      (node (ref "S$3") (pin "1") (pinfunction "1_1") (pintype "passive"))
    )
    (net (code "59") (name "Net-(B$4-PadOUT)") (class "Default")
      (node (ref "B$4") (pin "OUT") (pinfunction "OUT_OUT") (pintype "bidirectional"))
      (node (ref "E$1") (pin "RF$14_G4") (pinfunction "RF$14_G4_RF$14_G4") (pintype "bidirectional"))
    )
    (net (code "60") (name "Net-(B$5-PadHF)") (class "Default")
      (node (ref "B$5") (pin "HF") (pinfunction "HF_HF") (pintype "bidirectional"))
      (node (ref "S$2") (pin "1") (pinfunction "1_1") (pintype "passive"))
    )
    (net (code "61") (name "Net-(B$5-PadOUT)") (class "Default")
      (node (ref "B$5") (pin "OUT") (pinfunction "OUT_OUT") (pintype "bidirectional"))
      (node (ref "E$1") (pin "RF$16_G5") (pinfunction "RF$16_G5_RF$16_G5") (pintype "bidirectional"))
    )
    (net (code "62") (name "Net-(B$6-PadHF)") (class "Default")
      (node (ref "B$6") (pin "HF") (pinfunction "HF_HF") (pintype "bidirectional"))
      (node (ref "S$1") (pin "1") (pinfunction "1_1") (pintype "passive"))
    )
    (net (code "63") (name "Net-(B$6-PadOUT)") (class "Default")
      (node (ref "B$6") (pin "OUT") (pinfunction "OUT_OUT") (pintype "bidirectional"))
      (node (ref "E$1") (pin "RF$21_G6") (pinfunction "RF$21_G6_RF$21_G6") (pintype "bidirectional"))
    )
    (net (code "64") (name "Net-(B$8-PadOUT)") (class "Default")
      (node (ref "B$8") (pin "OUT") (pinfunction "OUT_OUT") (pintype "bidirectional"))
      (node (ref "L$2") (pin "IN") (pinfunction "IN_IN") (pintype "passive"))
    )
    (net (code "65") (name "Net-(B$9-PadOUT)") (class "Default")
      (node (ref "B$9") (pin "OUT") (pinfunction "OUT_OUT") (pintype "bidirectional"))
      (node (ref "L$3") (pin "IN") (pinfunction "IN_IN") (pintype "passive"))
    )
    (net (code "66") (name "Net-(E$1-DC§01)") (class "Default")
      (node (ref "E$1") (pin "DC$01") (pinfunction "DC§01_DC$01") (pintype "bidirectional"))
      (node (ref "R$1") (pin "OUT") (pinfunction "2_OUT") (pintype "passive"))
    )
    (net (code "67") (name "Net-(E$1-DC§019)") (class "Default")
      (node (ref "E$1") (pin "DC§19") (pinfunction "DC§019_DC§19") (pintype "bidirectional"))
      (node (ref "R$19") (pin "OUT") (pinfunction "2_OUT") (pintype "passive"))
    )
    (net (code "68") (name "Net-(E$1-PadRF$06_R1)") (class "Default")
      (node (ref "E$1") (pin "RF$06_R1") (pinfunction "RF$06_R1_RF$06_R1") (pintype "bidirectional"))
      (node (ref "L$2") (pin "OUT") (pinfunction "OUT_OUT") (pintype "passive"))
    )
    (net (code "69") (name "Net-(E$1-PadRF$12_R2)") (class "Default")
      (node (ref "E$1") (pin "RF$12_R2") (pinfunction "RF$12_R2_RF$12_R2") (pintype "bidirectional"))
      (node (ref "L$3") (pin "OUT") (pinfunction "OUT_OUT") (pintype "passive"))
    )
    (net (code "70") (name "Net-(E$1-PadRF$18_R3)") (class "Default")
      (node (ref "E$1") (pin "RF$18_R3") (pinfunction "RF$18_R3_RF$18_R3") (pintype "bidirectional"))
      (node (ref "L$4") (pin "OUT") (pinfunction "OUT_OUT") (pintype "passive"))
    )
    (net (code "71") (name "Net-(E$1-PadRF$24_R4)") (class "Default")
      (node (ref "E$1") (pin "RF$24_R4") (pinfunction "RF$24_R4_RF$24_R4") (pintype "bidirectional"))
      (node (ref "L$1") (pin "OUT") (pinfunction "OUT_OUT") (pintype "passive"))
    )
    (net (code "72") (name "Net-(R$2-2)") (class "Default")
      (node (ref "E$1") (pin "DC§02") (pinfunction "DC§02_DC§02") (pintype "bidirectional"))
      (node (ref "R$2") (pin "OUT") (pinfunction "2_OUT") (pintype "passive"))
    )
    (net (code "73") (name "Net-(R$3-2)") (class "Default")
      (node (ref "E$1") (pin "DC§03") (pinfunction "DC§03_DC§03") (pintype "bidirectional"))
      (node (ref "R$3") (pin "OUT") (pinfunction "2_OUT") (pintype "passive"))
    )
    (net (code "74") (name "Net-(R$4-2)") (class "Default")
      (node (ref "E$1") (pin "DC§04") (pinfunction "DC§04_DC§04") (pintype "bidirectional"))
      (node (ref "R$4") (pin "OUT") (pinfunction "2_OUT") (pintype "passive"))
    )
    (net (code "75") (name "Net-(R$5-2)") (class "Default")
      (node (ref "E$1") (pin "DC§05") (pinfunction "DC§05_DC§05") (pintype "bidirectional"))
      (node (ref "R$5") (pin "OUT") (pinfunction "2_OUT") (pintype "passive"))
    )
    (net (code "76") (name "Net-(R$6-2)") (class "Default")
      (node (ref "E$1") (pin "DC§06") (pinfunction "DC§06_DC§06") (pintype "bidirectional"))
      (node (ref "R$6") (pin "OUT") (pinfunction "2_OUT") (pintype "passive"))
    )
    (net (code "77") (name "Net-(R$7-2)") (class "Default")
      (node (ref "E$1") (pin "DC§08") (pinfunction "DC§08_DC§08") (pintype "bidirectional"))
      (node (ref "R$7") (pin "OUT") (pinfunction "2_OUT") (pintype "passive"))
    )
    (net (code "78") (name "Net-(R$8-2)") (class "Default")
      (node (ref "E$1") (pin "DC§09") (pinfunction "DC§09_DC§09") (pintype "bidirectional"))
      (node (ref "R$8") (pin "OUT") (pinfunction "2_OUT") (pintype "passive"))
    )
    (net (code "79") (name "Net-(R$9-2)") (class "Default")
      (node (ref "E$1") (pin "DC§10") (pinfunction "DC§10_DC§10") (pintype "bidirectional"))
      (node (ref "R$9") (pin "OUT") (pinfunction "2_OUT") (pintype "passive"))
    )
    (net (code "80") (name "Net-(R$10-2)") (class "Default")
      (node (ref "E$1") (pin "DC§11") (pinfunction "DC§11_DC§11") (pintype "bidirectional"))
      (node (ref "R$10") (pin "OUT") (pinfunction "2_OUT") (pintype "passive"))
    )
    (net (code "81") (name "Net-(R$11-2)") (class "Default")
      (node (ref "E$1") (pin "DC§12") (pinfunction "DC§12_DC§12") (pintype "bidirectional"))
      (node (ref "R$11") (pin "OUT") (pinfunction "2_OUT") (pintype "passive"))
    )
    (net (code "82") (name "Net-(R$12-2)") (class "Default")
      (node (ref "E$1") (pin "DC§13") (pinfunction "DC§13_DC§13") (pintype "bidirectional"))
      (node (ref "R$12") (pin "OUT") (pinfunction "2_OUT") (pintype "passive"))
    )
    (net (code "83") (name "Net-(R$20-2)") (class "Default")
      (node (ref "E$1") (pin "DC§20") (pinfunction "DC§20_DC§20") (pintype "bidirectional"))
      (node (ref "R$20") (pin "OUT") (pinfunction "2_OUT") (pintype "passive"))
    )
    (net (code "84") (name "Net-(R$21-2)") (class "Default")
      (node (ref "E$1") (pin "DC§21") (pinfunction "DC§21_DC§21") (pintype "bidirectional"))
      (node (ref "R$21") (pin "OUT") (pinfunction "2_OUT") (pintype "passive"))
    )
    (net (code "85") (name "Net-(R$22-2)") (class "Default")
      (node (ref "E$1") (pin "DC§22") (pinfunction "DC§22_DC§22") (pintype "bidirectional"))
      (node (ref "R$22") (pin "OUT") (pinfunction "2_OUT") (pintype "passive"))
    )
    (net (code "86") (name "Net-(R$23-2)") (class "Default")
      (node (ref "E$1") (pin "DC§23") (pinfunction "DC§23_DC§23") (pintype "bidirectional"))
      (node (ref "R$23") (pin "OUT") (pinfunction "2_OUT") (pintype "passive"))
    )
    (net (code "87") (name "Net-(R$24-2)") (class "Default")
      (node (ref "E$1") (pin "DC§24") (pinfunction "DC§24_DC§24") (pintype "bidirectional"))
      (node (ref "R$24") (pin "OUT") (pinfunction "2_OUT") (pintype "passive"))
    )
    (net (code "88") (name "Net-(R$25-2)") (class "Default")
      (node (ref "E$1") (pin "DC§07") (pinfunction "DC§07_DC§07") (pintype "bidirectional"))
      (node (ref "R$25") (pin "OUT") (pinfunction "2_OUT") (pintype "passive"))
    )
    (net (code "89") (name "Net-(R$26-2)") (class "Default")
      (node (ref "E$1") (pin "DC§14") (pinfunction "DC§14_DC§14") (pintype "bidirectional"))
      (node (ref "R$26") (pin "OUT") (pinfunction "2_OUT") (pintype "passive"))
    )
    (net (code "90") (name "Net-(R$27-2)") (class "Default")
      (node (ref "E$1") (pin "DC§15") (pinfunction "DC§15_DC§15") (pintype "bidirectional"))
      (node (ref "R$27") (pin "OUT") (pinfunction "2_OUT") (pintype "passive"))
    )
    (net (code "91") (name "Net-(R$28-2)") (class "Default")
      (node (ref "E$1") (pin "DC§16") (pinfunction "DC§16_DC§16") (pintype "bidirectional"))
      (node (ref "R$28") (pin "OUT") (pinfunction "2_OUT") (pintype "passive"))
    )
    (net (code "92") (name "Net-(R$29-2)") (class "Default")
      (node (ref "E$1") (pin "DC§17") (pinfunction "DC§17_DC§17") (pintype "bidirectional"))
      (node (ref "R$29") (pin "OUT") (pinfunction "2_OUT") (pintype "passive"))
    )
    (net (code "93") (name "Net-(R$30-2)") (class "Default")
      (node (ref "E$1") (pin "DC§18") (pinfunction "DC§18_DC§18") (pintype "bidirectional"))
      (node (ref "R$30") (pin "OUT") (pinfunction "2_OUT") (pintype "passive"))
    )
    (net (code "94") (name "Net-(U$3-IN)") (class "Default")
      (node (ref "U$3") (pin "P$1") (pinfunction "IN_P$1") (pintype "bidirectional"))
      (node (ref "U$4") (pin "P$3") (pinfunction "OUT2_P$3") (pintype "bidirectional"))
    )
    (net (code "95") (name "Net-(U$3-OUT1)") (class "Default")
      (node (ref "B$8") (pin "HF") (pinfunction "HF_HF") (pintype "bidirectional"))
      (node (ref "U$3") (pin "P$2") (pinfunction "OUT1_P$2") (pintype "bidirectional"))
    )
    (net (code "96") (name "Net-(U$3-OUT2)") (class "Default")
      (node (ref "B$7") (pin "HF") (pinfunction "HF_HF") (pintype "bidirectional"))
      (node (ref "U$3") (pin "P$3") (pinfunction "OUT2_P$3") (pintype "bidirectional"))
    )
    (net (code "97") (name "Net-(U$4-IN)") (class "Default")
      (node (ref "S$5") (pin "1") (pinfunction "1_1") (pintype "passive"))
      (node (ref "U$4") (pin "P$1") (pinfunction "IN_P$1") (pintype "bidirectional"))
    )
    (net (code "98") (name "Net-(U$4-OUT1)") (class "Default")
      (node (ref "U$4") (pin "P$2") (pinfunction "OUT1_P$2") (pintype "bidirectional"))
      (node (ref "U$5") (pin "P$1") (pinfunction "IN_P$1") (pintype "bidirectional"))
    )
    (net (code "99") (name "Net-(U$5-OUT1)") (class "Default")
      (node (ref "B$10") (pin "HF") (pinfunction "HF_HF") (pintype "bidirectional"))
      (node (ref "U$5") (pin "P$2") (pinfunction "OUT1_P$2") (pintype "bidirectional"))
    )
    (net (code "100") (name "Net-(U$5-OUT2)") (class "Default")
      (node (ref "B$9") (pin "HF") (pinfunction "HF_HF") (pintype "bidirectional"))
      (node (ref "U$5") (pin "P$3") (pinfunction "OUT2_P$3") (pintype "bidirectional"))
    )
    (net (code "101") (name "unconnected-(U$2-PadI$1)") (class "Default")
      (node (ref "U$2") (pin "I$1") (pinfunction "I$1_I$1") (pintype "bidirectional"))
    )
    (net (code "102") (name "unconnected-(U$2-PadI$2)") (class "Default")
      (node (ref "U$2") (pin "I$2") (pinfunction "I$2_I$2") (pintype "bidirectional"))
    )
    (net (code "103") (name "unconnected-(U$2-PadU$1)") (class "Default")
      (node (ref "U$2") (pin "U$1") (pinfunction "U$1_U$1") (pintype "bidirectional"))
    )
    (net (code "104") (name "unconnected-(U$2-PadU$2)") (class "Default")
      (node (ref "U$2") (pin "U$2") (pinfunction "U$2_U$2") (pintype "bidirectional"))
    )
  )
)
